# RX-FM-Super-Regenerative-FM.net
KiCad netlist of a schematic drawn in EAGLE
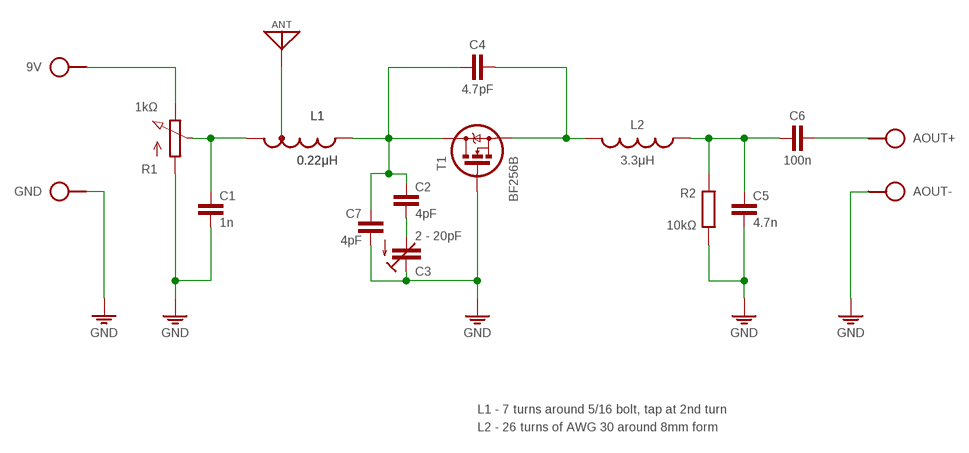
[diagram p0: schematic, sheet 1]

(export (version "E")
  (design (tool "Eeschema 10.0.6"))
  (components
    (comp (ref "9V")
      (value "SPAD")
      (footprint "eagle-import:SPAD")
      (libsource (lib "eagle-import") (part "SPAD"))
    )
    (comp (ref "ANT")
      (value "ANT")
      (footprint "eagle-import:SPAD")
      (libsource (lib "eagle-import") (part "ANT"))
    )
    (comp (ref "AOUT+")
      (value "SPAD")
      (footprint "eagle-import:SPAD")
      (libsource (lib "eagle-import") (part "SPAD"))
    )
    (comp (ref "AOUT-")
      (value "SPAD")
      (footprint "eagle-import:SPAD")
      (libsource (lib "eagle-import") (part "SPAD"))
    )
    (comp (ref "C1")
      (value "1n")
      (footprint "eagle-import:C050-020X036_V")
      (libsource (lib "eagle-import") (part "C050-020X036/V"))
    )
    (comp (ref "C2")
      (value "4pF")
      (footprint "eagle-import:C025-015X024")
      (libsource (lib "eagle-import") (part "C025-015X024"))
    )
    (comp (ref "C3")
      (value "2 - 20pF")
      (footprint "eagle-import:TRIM-2222-808")
      (libsource (lib "eagle-import") (part "C-TR-PH201272222-808-2PIN"))
    )
    (comp (ref "C4")
      (value "4.7pF")
      (footprint "eagle-import:C050-020X036")
      (libsource (lib "eagle-import") (part "C050-020X036"))
    )
    (comp (ref "C5")
      (value "4.7n")
      (footprint "eagle-import:C050-020X044")
      (libsource (lib "eagle-import") (part "C050-020X044"))
    )
    (comp (ref "C6")
      (value "100n")
      (footprint "eagle-import:C050-020X044")
      (libsource (lib "eagle-import") (part "C050-020X044"))
    )
    (comp (ref "C7")
      (value "4pF")
      (footprint "eagle-import:C025-015X024")
      (libsource (lib "eagle-import") (part "C025-015X024"))
    )
    (comp (ref "GND")
      (value "SPAD")
      (footprint "eagle-import:SPAD")
      (libsource (lib "eagle-import") (part "SPAD"))
    )
    (comp (ref "L1")
      (value "0.22μH")
      (footprint "eagle-import:L-08_12-X-TAP1")
      (libsource (lib "eagle-import") (part "L-TAP1L-08/12-X-TAP1"))
    )
    (comp (ref "L2")
      (value "3.3μH")
      (footprint "eagle-import:L-BODY")
      (libsource (lib "eagle-import") (part "L-BODY"))
    )
    (comp (ref "R1")
      (value "1kΩ")
      (footprint "eagle-import:POT-V")
      (libsource (lib "eagle-import") (part "POT-V"))
    )
    (comp (ref "R2")
      (value "10kΩ")
      (footprint "eagle-import:0204_10")
      (libsource (lib "eagle-import") (part "R0204/10"))
    )
    (comp (ref "T1")
      (value "BF256B")
      (footprint "eagle-import:TO92")
      (libsource (lib "eagle-import") (part "BF256B"))
    )
  )
  (nets
    (net (code "1") (name "GND") (class "Default")
      (node (ref "AOUT-") (pin "1") (pinfunction "P$1_1") (pintype "bidirectional"))
      (node (ref "C1") (pin "2") (pinfunction "2_2") (pintype "passive"))
      (node (ref "C3") (pin "2") (pinfunction "E_2") (pintype "passive"))
      (node (ref "C5") (pin "2") (pinfunction "2_2") (pintype "passive"))
      (node (ref "C7") (pin "2") (pinfunction "2_2") (pintype "passive"))
      (node (ref "GND") (pin "1") (pinfunction "P$1_1") (pintype "bidirectional"))
      (node (ref "R1") (pin "A") (pinfunction "A_A") (pintype "passive"))
      (node (ref "R2") (pin "1") (pinfunction "1_1") (pintype "passive"))
      (node (ref "T1") (pin "1") (pinfunction "G_1") (pintype "passive"))
    )
    (net (code "2") (name "Net-(9V-P$1)") (class "Default")
      (node (ref "9V") (pin "1") (pinfunction "P$1_1") (pintype "bidirectional"))
      (node (ref "R1") (pin "E") (pinfunction "E_E") (pintype "passive"))
    )
    (net (code "3") (name "Net-(AOUT+-P$1)") (class "Default")
      (node (ref "AOUT+") (pin "1") (pinfunction "P$1_1") (pintype "bidirectional"))
      (node (ref "C6") (pin "2") (pinfunction "2_2") (pintype "passive"))
    )
    (net (code "4") (name "Net-(C1-Pad1)") (class "Default")
      (node (ref "C1") (pin "1") (pinfunction "1_1") (pintype "passive"))
      (node (ref "L1") (pin "1") (pinfunction "1_1") (pintype "passive"))
      (node (ref "R1") (pin "S") (pinfunction "S_S") (pintype "passive"))
    )
    (net (code "5") (name "Net-(C3-A)") (class "Default")
      (node (ref "C2") (pin "2") (pinfunction "2_2") (pintype "passive"))
      (node (ref "C3") (pin "1") (pinfunction "A_1") (pintype "passive"))
    )
    (net (code "6") (name "Net-(L1-T)") (class "Default")
      (node (ref "ANT") (pin "1") (pinfunction "1_1") (pintype "output"))
      (node (ref "L1") (pin "3") (pinfunction "T_3") (pintype "passive"))
    )
    (net (code "7") (name "Net-(L2-1)") (class "Default")
      (node (ref "C5") (pin "1") (pinfunction "1_1") (pintype "passive"))
      (node (ref "C6") (pin "1") (pinfunction "1_1") (pintype "passive"))
      (node (ref "L2") (pin "2") (pinfunction "1_2") (pintype "passive"))
      (node (ref "R2") (pin "2") (pinfunction "2_2") (pintype "passive"))
    )
    (net (code "8") (name "Net-(L2-2)") (class "Default")
      (node (ref "C4") (pin "2") (pinfunction "2_2") (pintype "passive"))
      (node (ref "L2") (pin "3") (pinfunction "2_3") (pintype "passive"))
      (node (ref "T1") (pin "2") (pinfunction "S_2") (pintype "passive"))
    )
    (net (code "9") (name "Net-(T1-D)") (class "Default")
      (node (ref "C2") (pin "1") (pinfunction "1_1") (pintype "passive"))
      (node (ref "C4") (pin "1") (pinfunction "1_1") (pintype "passive"))
      (node (ref "C7") (pin "1") (pinfunction "1_1") (pintype "passive"))
      (node (ref "L1") (pin "2") (pinfunction "2_2") (pintype "passive"))
      (node (ref "T1") (pin "3") (pinfunction "D_3") (pintype "passive"))
    )
  )
)
